# nrf51822.net
KiCad netlist of a schematic drawn in EAGLE
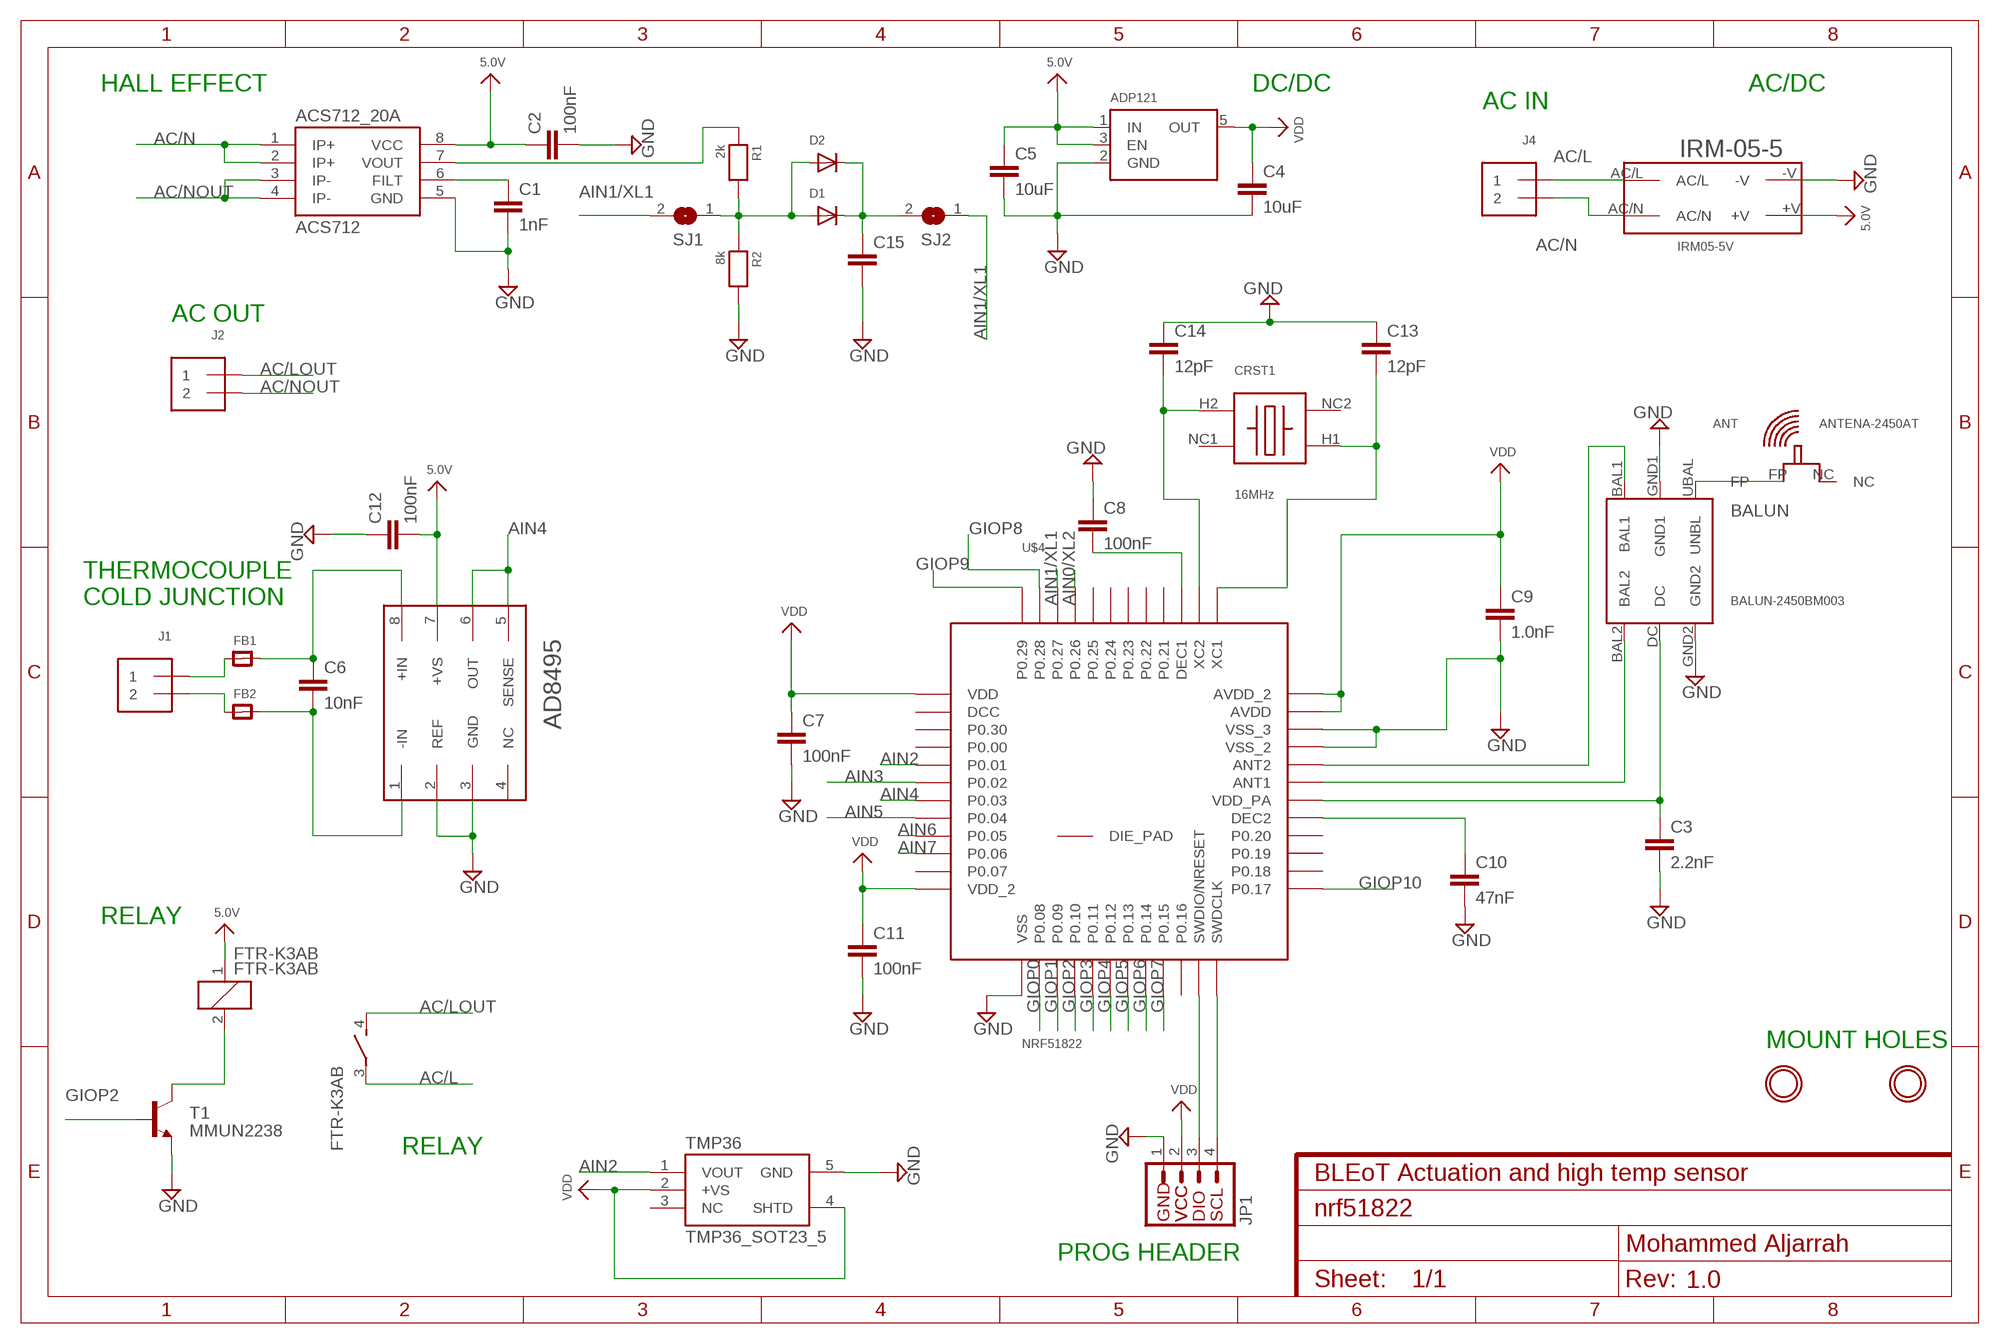
[diagram p0: schematic, sheet 1]

(export (version "E")
  (design (tool "Eeschema 10.0.6"))
  (components
    (comp (ref "ACS712_20A")
      (value "ACS712")
      (footprint "eagle-import:SO08")
      (libsource (lib "eagle-import") (part "ACS712"))
    )
    (comp (ref "AD8495")
      (value "AD8495")
      (footprint "eagle-import:MSOP-8")
      (libsource (lib "eagle-import") (part "AD8495"))
    )
    (comp (ref "ADP121")
      (value "ADP121")
      (footprint "eagle-import:SOT23-5")
      (libsource (lib "eagle-import") (part "ADP121"))
    )
    (comp (ref "ANT")
      (value "ANTENA-2450AT")
      (footprint "eagle-import:2450AT18B100")
      (libsource (lib "eagle-import") (part "ANTENA-2450AT"))
    )
    (comp (ref "BALUN")
      (value "BALUN-2450BM003")
      (footprint "eagle-import:2450BM14E0003")
      (libsource (lib "eagle-import") (part "BALUN-2450BM003"))
    )
    (comp (ref "C1")
      (value "1nF")
      (footprint "eagle-import:C0805")
      (libsource (lib "eagle-import") (part "C-EUC0805"))
    )
    (comp (ref "C2")
      (value "100nF")
      (footprint "eagle-import:C0805")
      (libsource (lib "eagle-import") (part "C-EUC0805"))
    )
    (comp (ref "C3")
      (value "2.2nF")
      (footprint "eagle-import:C0805")
      (libsource (lib "eagle-import") (part "C-EUC0805"))
    )
    (comp (ref "C4")
      (value "10uF")
      (footprint "eagle-import:C0805")
      (libsource (lib "eagle-import") (part "C-EUC0805"))
    )
    (comp (ref "C5")
      (value "10uF")
      (footprint "eagle-import:C0805")
      (libsource (lib "eagle-import") (part "C-EUC0805"))
    )
    (comp (ref "C6")
      (value "10nF")
      (footprint "eagle-import:C0805")
      (libsource (lib "eagle-import") (part "C-EUC0805"))
    )
    (comp (ref "C7")
      (value "100nF")
      (footprint "eagle-import:C0805")
      (libsource (lib "eagle-import") (part "C-EUC0805"))
    )
    (comp (ref "C8")
      (value "100nF")
      (footprint "eagle-import:C0805")
      (libsource (lib "eagle-import") (part "C-EUC0805"))
    )
    (comp (ref "C9")
      (value "1.0nF")
      (footprint "eagle-import:C0805")
      (libsource (lib "eagle-import") (part "C-EUC0805"))
    )
    (comp (ref "C10")
      (value "47nF")
      (footprint "eagle-import:C0805")
      (libsource (lib "eagle-import") (part "C-EUC0805"))
    )
    (comp (ref "C11")
      (value "100nF")
      (footprint "eagle-import:C0805")
      (libsource (lib "eagle-import") (part "C-EUC0805"))
    )
    (comp (ref "C12")
      (value "100nF")
      (footprint "eagle-import:C0805")
      (libsource (lib "eagle-import") (part "C-EUC0805"))
    )
    (comp (ref "C13")
      (value "12pF")
      (footprint "eagle-import:C0805")
      (libsource (lib "eagle-import") (part "C-EUC0805"))
    )
    (comp (ref "C14")
      (value "12pF")
      (footprint "eagle-import:C0805")
      (libsource (lib "eagle-import") (part "C-EUC0805"))
    )
    (comp (ref "C15")
      (value "CAPPTH3")
      (footprint "eagle-import:CAP-PTH-LARGE")
      (libsource (lib "eagle-import") (part "CAPPTH3"))
    )
    (comp (ref "CRST1")
      (value "16MHz")
      (footprint "eagle-import:CRYSTAL16MHZ")
      (libsource (lib "eagle-import") (part "CX3225GB"))
    )
    (comp (ref "D1")
      (value "DIODESOD-123")
      (footprint "eagle-import:SOD-123")
      (libsource (lib "eagle-import") (part "DIODESOD-123"))
    )
    (comp (ref "D2")
      (value "DIODEDO-1N4148")
      (footprint "eagle-import:DO-1N4148")
      (libsource (lib "eagle-import") (part "microbuilder_DIODEDO-1N4148"))
    )
    (comp (ref "FB1")
      (value "FERRITE0805")
      (footprint "eagle-import:0805")
      (libsource (lib "eagle-import") (part "FERRITE0805"))
    )
    (comp (ref "FB2")
      (value "FERRITE0805")
      (footprint "eagle-import:0805")
      (libsource (lib "eagle-import") (part "FERRITE0805"))
    )
    (comp (ref "FTR-K3AB")
      (value "FTR-K3AB")
      (footprint "eagle-import:FTR-K1C")
      (libsource (lib "eagle-import") (part "FTR-K3AB"))
    )
    (comp (ref "IRM-05-5")
      (value "IRM05-5V")
      (footprint "eagle-import:IRM05")
      (libsource (lib "eagle-import") (part "IRM05-5V"))
    )
    (comp (ref "J1")
      (value "TERMBLOCK_1X2")
      (footprint "eagle-import:TERMBLOCK_1X2-3.5MM")
      (libsource (lib "eagle-import") (part "TERMBLOCK_1X2"))
    )
    (comp (ref "J2")
      (value "TERMBLOCK_1X2")
      (footprint "eagle-import:TERMBLOCK_1X2-3.5MM")
      (libsource (lib "eagle-import") (part "TERMBLOCK_1X2"))
    )
    (comp (ref "J4")
      (value "TERMBLOCK_1X2")
      (footprint "eagle-import:TERMBLOCK_1X2-3.5MM")
      (libsource (lib "eagle-import") (part "TERMBLOCK_1X2"))
    )
    (comp (ref "JP1")
      (value "PROG_HEADER")
      (footprint "eagle-import:1X04")
      (libsource (lib "eagle-import") (part "PROG_HEADER"))
    )
    (comp (ref "R1")
      (value "2k")
      (footprint "eagle-import:0805")
      (libsource (lib "eagle-import") (part "RESISTOR0805"))
    )
    (comp (ref "R2")
      (value "8k")
      (footprint "eagle-import:0805")
      (libsource (lib "eagle-import") (part "RESISTOR0805"))
    )
    (comp (ref "SJ1")
      (value "SOLDERJUMPERREFLOW_NOPASTE")
      (footprint "eagle-import:SOLDERJUMPER_REFLOW_NOPASTE")
      (libsource (lib "eagle-import") (part "SOLDERJUMPERREFLOW_NOPASTE"))
    )
    (comp (ref "SJ2")
      (value "SOLDERJUMPERREFLOW_NOPASTE")
      (footprint "eagle-import:SOLDERJUMPER_REFLOW_NOPASTE")
      (libsource (lib "eagle-import") (part "SOLDERJUMPERREFLOW_NOPASTE"))
    )
    (comp (ref "T1")
      (value "MMUN2238")
      (footprint "eagle-import:SOT23-3")
      (libsource (lib "eagle-import") (part "TRANSISTOR_NPNMMBT2222A"))
    )
    (comp (ref "TMP36")
      (value "TMP36_SOT23_5")
      (footprint "eagle-import:SOT23-5")
      (libsource (lib "eagle-import") (part "TMP36_SOT23_5"))
    )
    (comp (ref "U$1")
      (value "MOUNTINGHOLE2.5")
      (footprint "eagle-import:MOUNTINGHOLE_2.5_PLATED")
      (libsource (lib "eagle-import") (part "MOUNTINGHOLE2.5"))
    )
    (comp (ref "U$4")
      (value "NRF51822")
      (footprint "eagle-import:QFN48")
      (libsource (lib "eagle-import") (part "NRF51822"))
    )
    (comp (ref "U$7")
      (value "MOUNTINGHOLE2.5")
      (footprint "eagle-import:MOUNTINGHOLE_2.5_PLATED")
      (libsource (lib "eagle-import") (part "MOUNTINGHOLE2.5"))
    )
  )
  (nets
    (net (code "1") (name "/AC{slash}L") (class "Default")
      (node (ref "FTR-K3AB") (pin "3") (pinfunction "3_3") (pintype "passive"))
      (node (ref "IRM-05-5") (pin "AC/L") (pinfunction "AC/L_AC/L") (pintype "input"))
      (node (ref "J4") (pin "1") (pinfunction "1_1") (pintype "passive"))
    )
    (net (code "2") (name "/AC{slash}LOUT") (class "Default")
      (node (ref "FTR-K3AB") (pin "4") (pinfunction "4_4") (pintype "passive"))
      (node (ref "J2") (pin "1") (pinfunction "1_1") (pintype "passive"))
    )
    (net (code "3") (name "/AC{slash}N") (class "Default")
      (node (ref "ACS712_20A") (pin "1") (pinfunction "IP+_1") (pintype "bidirectional"))
      (node (ref "ACS712_20A") (pin "2") (pinfunction "IP+_2") (pintype "bidirectional"))
      (node (ref "IRM-05-5") (pin "AC/N") (pinfunction "AC/N_AC/N") (pintype "input"))
      (node (ref "J4") (pin "2") (pinfunction "2_2") (pintype "passive"))
    )
    (net (code "4") (name "/AC{slash}NOUT") (class "Default")
      (node (ref "ACS712_20A") (pin "3") (pinfunction "IP-_3") (pintype "bidirectional"))
      (node (ref "ACS712_20A") (pin "4") (pinfunction "IP-_4") (pintype "bidirectional"))
      (node (ref "J2") (pin "2") (pinfunction "2_2") (pintype "passive"))
    )
    (net (code "5") (name "/AIN0{slash}XL2") (class "Default")
      (node (ref "U$4") (pin "45") (pinfunction "P0.26_45") (pintype "bidirectional"))
    )
    (net (code "6") (name "/AIN1{slash}XL1") (class "Default")
      (node (ref "SJ1") (pin "2") (pinfunction "2_2") (pintype "passive"))
      (node (ref "SJ2") (pin "1") (pinfunction "1_1") (pintype "passive"))
      (node (ref "U$4") (pin "46") (pinfunction "P0.27_46") (pintype "bidirectional"))
    )
    (net (code "7") (name "/AIN2") (class "Default")
      (node (ref "TMP36") (pin "1") (pinfunction "VOUT_1") (pintype "output"))
      (node (ref "U$4") (pin "5") (pinfunction "P0.01_5") (pintype "bidirectional"))
    )
    (net (code "8") (name "/AIN3") (class "Default")
      (node (ref "U$4") (pin "6") (pinfunction "P0.02_6") (pintype "bidirectional"))
    )
    (net (code "9") (name "/AIN4") (class "Default")
      (node (ref "AD8495") (pin "5") (pinfunction "SENSE_5") (pintype "bidirectional"))
      (node (ref "AD8495") (pin "6") (pinfunction "OUT_6") (pintype "output"))
      (node (ref "U$4") (pin "7") (pinfunction "P0.03_7") (pintype "bidirectional"))
    )
    (net (code "10") (name "/AIN5") (class "Default")
      (node (ref "U$4") (pin "8") (pinfunction "P0.04_8") (pintype "bidirectional"))
    )
    (net (code "11") (name "/AIN6") (class "Default")
      (node (ref "U$4") (pin "9") (pinfunction "P0.05_9") (pintype "bidirectional"))
    )
    (net (code "12") (name "/AIN7") (class "Default")
      (node (ref "U$4") (pin "10") (pinfunction "P0.06_10") (pintype "bidirectional"))
    )
    (net (code "13") (name "/GIOP0") (class "Default")
      (node (ref "U$4") (pin "14") (pinfunction "P0.08_14") (pintype "bidirectional"))
    )
    (net (code "14") (name "/GIOP1") (class "Default")
      (node (ref "U$4") (pin "15") (pinfunction "P0.09_15") (pintype "bidirectional"))
    )
    (net (code "15") (name "/GIOP2") (class "Default")
      (node (ref "T1") (pin "1") (pinfunction "B_1") (pintype "passive"))
      (node (ref "U$4") (pin "16") (pinfunction "P0.10_16") (pintype "bidirectional"))
    )
    (net (code "16") (name "/GIOP3") (class "Default")
      (node (ref "U$4") (pin "17") (pinfunction "P0.11_17") (pintype "bidirectional"))
    )
    (net (code "17") (name "/GIOP4") (class "Default")
      (node (ref "U$4") (pin "18") (pinfunction "P0.12_18") (pintype "bidirectional"))
    )
    (net (code "18") (name "/GIOP5") (class "Default")
      (node (ref "U$4") (pin "19") (pinfunction "P0.13_19") (pintype "bidirectional"))
    )
    (net (code "19") (name "/GIOP6") (class "Default")
      (node (ref "U$4") (pin "20") (pinfunction "P0.14_20") (pintype "bidirectional"))
    )
    (net (code "20") (name "/GIOP7") (class "Default")
      (node (ref "U$4") (pin "21") (pinfunction "P0.15_21") (pintype "bidirectional"))
    )
    (net (code "21") (name "/GIOP8") (class "Default")
      (node (ref "U$4") (pin "47") (pinfunction "P0.28_47") (pintype "bidirectional"))
    )
    (net (code "22") (name "/GIOP9") (class "Default")
      (node (ref "U$4") (pin "48") (pinfunction "P0.29_48") (pintype "bidirectional"))
    )
    (net (code "23") (name "/GIOP10") (class "Default")
      (node (ref "U$4") (pin "25") (pinfunction "P0.17_25") (pintype "bidirectional"))
    )
    (net (code "24") (name "5.0V") (class "Default")
      (node (ref "ACS712_20A") (pin "8") (pinfunction "VCC_8") (pintype "bidirectional"))
      (node (ref "AD8495") (pin "7") (pinfunction "+VS_7") (pintype "power_in"))
      (node (ref "ADP121") (pin "1") (pinfunction "IN_1") (pintype "bidirectional"))
      (node (ref "ADP121") (pin "3") (pinfunction "EN_3") (pintype "bidirectional"))
      (node (ref "C12") (pin "2") (pinfunction "2_2") (pintype "passive"))
      (node (ref "C2") (pin "1") (pinfunction "1_1") (pintype "passive"))
      (node (ref "C5") (pin "1") (pinfunction "1_1") (pintype "passive"))
      (node (ref "FTR-K3AB") (pin "1") (pinfunction "1_1") (pintype "power_in"))
      (node (ref "IRM-05-5") (pin "+V") (pinfunction "+V_+V") (pintype "power_in"))
    )
    (net (code "25") (name "GND") (class "Default")
      (node (ref "ACS712_20A") (pin "5") (pinfunction "GND_5") (pintype "bidirectional"))
      (node (ref "AD8495") (pin "2") (pinfunction "REF_2") (pintype "power_in"))
      (node (ref "AD8495") (pin "3") (pinfunction "GND_3") (pintype "power_in"))
      (node (ref "ADP121") (pin "2") (pinfunction "GND_2") (pintype "bidirectional"))
      (node (ref "BALUN") (pin "GND1") (pinfunction "GND1_GND1") (pintype "power_in"))
      (node (ref "BALUN") (pin "GND2") (pinfunction "GND2_GND2") (pintype "power_in"))
      (node (ref "C1") (pin "2") (pinfunction "2_2") (pintype "passive"))
      (node (ref "C10") (pin "2") (pinfunction "2_2") (pintype "passive"))
      (node (ref "C11") (pin "2") (pinfunction "2_2") (pintype "passive"))
      (node (ref "C12") (pin "1") (pinfunction "1_1") (pintype "passive"))
      (node (ref "C13") (pin "1") (pinfunction "1_1") (pintype "passive"))
      (node (ref "C14") (pin "1") (pinfunction "1_1") (pintype "passive"))
      (node (ref "C15") (pin "2") (pinfunction "2_2") (pintype "passive"))
      (node (ref "C2") (pin "2") (pinfunction "2_2") (pintype "passive"))
      (node (ref "C3") (pin "2") (pinfunction "2_2") (pintype "passive"))
      (node (ref "C4") (pin "2") (pinfunction "2_2") (pintype "passive"))
      (node (ref "C5") (pin "2") (pinfunction "2_2") (pintype "passive"))
      (node (ref "C7") (pin "2") (pinfunction "2_2") (pintype "passive"))
      (node (ref "C8") (pin "1") (pinfunction "1_1") (pintype "passive"))
      (node (ref "C9") (pin "2") (pinfunction "2_2") (pintype "passive"))
      (node (ref "IRM-05-5") (pin "-V") (pinfunction "-V_-V") (pintype "power_in"))
      (node (ref "JP1") (pin "1") (pinfunction "1_1") (pintype "passive"))
      (node (ref "R2") (pin "2") (pinfunction "2_2") (pintype "passive"))
      (node (ref "T1") (pin "2") (pinfunction "E_2") (pintype "passive"))
      (node (ref "TMP36") (pin "5") (pinfunction "GND_5") (pintype "power_in"))
      (node (ref "U$4") (pin "13") (pinfunction "VSS_13") (pintype "power_in"))
      (node (ref "U$4") (pin "33") (pinfunction "VSS_2_33") (pintype "power_in"))
      (node (ref "U$4") (pin "34") (pinfunction "VSS_3_34") (pintype "power_in"))
    )
    (net (code "26") (name "Net-(ACS712_20A-FILT)") (class "Default")
      (node (ref "ACS712_20A") (pin "6") (pinfunction "FILT_6") (pintype "bidirectional"))
      (node (ref "C1") (pin "1") (pinfunction "1_1") (pintype "passive"))
    )
    (net (code "27") (name "Net-(ACS712_20A-VOUT)") (class "Default")
      (node (ref "ACS712_20A") (pin "7") (pinfunction "VOUT_7") (pintype "bidirectional"))
      (node (ref "R1") (pin "1") (pinfunction "1_1") (pintype "passive"))
    )
    (net (code "28") (name "Net-(AD8495-+IN)") (class "Default")
      (node (ref "AD8495") (pin "8") (pinfunction "+IN_8") (pintype "input"))
      (node (ref "C6") (pin "1") (pinfunction "1_1") (pintype "passive"))
      (node (ref "FB1") (pin "2") (pinfunction "P$2_2") (pintype "passive"))
    )
    (net (code "29") (name "Net-(AD8495--IN)") (class "Default")
      (node (ref "AD8495") (pin "1") (pinfunction "-IN_1") (pintype "input"))
      (node (ref "C6") (pin "2") (pinfunction "2_2") (pintype "passive"))
      (node (ref "FB2") (pin "2") (pinfunction "P$2_2") (pintype "passive"))
    )
    (net (code "30") (name "Net-(BALUN-UNBL)") (class "Default")
      (node (ref "ANT") (pin "FP") (pinfunction "FP_FP") (pintype "input"))
      (node (ref "BALUN") (pin "UBAL") (pinfunction "UNBL_UBAL") (pintype "output"))
    )
    (net (code "31") (name "Net-(C15-Pad1)") (class "Default")
      (node (ref "C15") (pin "1") (pinfunction "1_1") (pintype "passive"))
      (node (ref "D1") (pin "C") (pinfunction "C_C") (pintype "passive"))
      (node (ref "D2") (pin "C") (pinfunction "C_C") (pintype "passive"))
      (node (ref "SJ2") (pin "2") (pinfunction "2_2") (pintype "passive"))
    )
    (net (code "32") (name "Net-(D1-PadA)") (class "Default")
      (node (ref "D1") (pin "A") (pinfunction "A_A") (pintype "passive"))
      (node (ref "D2") (pin "A") (pinfunction "A_A") (pintype "passive"))
      (node (ref "R1") (pin "2") (pinfunction "2_2") (pintype "passive"))
      (node (ref "R2") (pin "1") (pinfunction "1_1") (pintype "passive"))
      (node (ref "SJ1") (pin "1") (pinfunction "1_1") (pintype "passive"))
    )
    (net (code "33") (name "Net-(FB1-P$1)") (class "Default")
      (node (ref "FB1") (pin "1") (pinfunction "P$1_1") (pintype "passive"))
      (node (ref "J1") (pin "1") (pinfunction "1_1") (pintype "passive"))
    )
    (net (code "34") (name "Net-(FB2-P$1)") (class "Default")
      (node (ref "FB2") (pin "1") (pinfunction "P$1_1") (pintype "passive"))
      (node (ref "J1") (pin "2") (pinfunction "2_2") (pintype "passive"))
    )
    (net (code "35") (name "Net-(T1-C)") (class "Default")
      (node (ref "FTR-K3AB") (pin "2") (pinfunction "2_2") (pintype "power_in"))
      (node (ref "T1") (pin "3") (pinfunction "C_3") (pintype "passive"))
    )
    (net (code "36") (name "Net-(U$4-ANT1)") (class "Default")
      (node (ref "BALUN") (pin "BAL2") (pinfunction "BAL2_BAL2") (pintype "input"))
      (node (ref "U$4") (pin "31") (pinfunction "ANT1_31") (pintype "bidirectional"))
    )
    (net (code "37") (name "Net-(U$4-ANT2)") (class "Default")
      (node (ref "BALUN") (pin "BAL1") (pinfunction "BAL1_BAL1") (pintype "input"))
      (node (ref "U$4") (pin "32") (pinfunction "ANT2_32") (pintype "bidirectional"))
    )
    (net (code "38") (name "Net-(U$4-DEC1)") (class "Default")
      (node (ref "C8") (pin "2") (pinfunction "2_2") (pintype "passive"))
      (node (ref "U$4") (pin "39") (pinfunction "DEC1_39") (pintype "bidirectional"))
    )
    (net (code "39") (name "Net-(U$4-DEC2)") (class "Default")
      (node (ref "C10") (pin "1") (pinfunction "1_1") (pintype "passive"))
      (node (ref "U$4") (pin "29") (pinfunction "DEC2_29") (pintype "bidirectional"))
    )
    (net (code "40") (name "Net-(U$4-SWDCLK)") (class "Default")
      (node (ref "JP1") (pin "4") (pinfunction "4_4") (pintype "passive"))
      (node (ref "U$4") (pin "24") (pinfunction "SWDCLK_24") (pintype "bidirectional"))
    )
    (net (code "41") (name "Net-(U$4-SWDIO{slash}NRESET)") (class "Default")
      (node (ref "JP1") (pin "3") (pinfunction "3_3") (pintype "passive"))
      (node (ref "U$4") (pin "23") (pinfunction "SWDIO/NRESET_23") (pintype "bidirectional"))
    )
    (net (code "42") (name "Net-(U$4-VDD_PA)") (class "Default")
      (node (ref "BALUN") (pin "DC") (pinfunction "DC_DC") (pintype "power_in"))
      (node (ref "C3") (pin "1") (pinfunction "1_1") (pintype "passive"))
      (node (ref "U$4") (pin "30") (pinfunction "VDD_PA_30") (pintype "bidirectional"))
    )
    (net (code "43") (name "Net-(U$4-XC1)") (class "Default")
      (node (ref "C13") (pin "2") (pinfunction "2_2") (pintype "passive"))
      (node (ref "CRST1") (pin "H1") (pinfunction "H1_H1") (pintype "input"))
      (node (ref "U$4") (pin "37") (pinfunction "XC1_37") (pintype "bidirectional"))
    )
    (net (code "44") (name "Net-(U$4-XC2)") (class "Default")
      (node (ref "C14") (pin "2") (pinfunction "2_2") (pintype "passive"))
      (node (ref "CRST1") (pin "H2") (pinfunction "H2_H2") (pintype "input"))
      (node (ref "U$4") (pin "38") (pinfunction "XC2_38") (pintype "bidirectional"))
    )
    (net (code "45") (name "VDD") (class "Default")
      (node (ref "ADP121") (pin "5") (pinfunction "OUT_5") (pintype "bidirectional"))
      (node (ref "C11") (pin "1") (pinfunction "1_1") (pintype "passive"))
      (node (ref "C4") (pin "1") (pinfunction "1_1") (pintype "passive"))
      (node (ref "C7") (pin "1") (pinfunction "1_1") (pintype "passive"))
      (node (ref "C9") (pin "1") (pinfunction "1_1") (pintype "passive"))
      (node (ref "JP1") (pin "2") (pinfunction "2_2") (pintype "passive"))
      (node (ref "TMP36") (pin "2") (pinfunction "+VS_2") (pintype "power_in"))
      (node (ref "TMP36") (pin "4") (pinfunction "SHTD_4") (pintype "input"))
      (node (ref "U$4") (pin "1") (pinfunction "VDD_1") (pintype "power_in"))
      (node (ref "U$4") (pin "12") (pinfunction "VDD_2_12") (pintype "power_in"))
      (node (ref "U$4") (pin "35") (pinfunction "AVDD_35") (pintype "power_in"))
      (node (ref "U$4") (pin "36") (pinfunction "AVDD_2_36") (pintype "power_in"))
    )
    (net (code "46") (name "unconnected-(AD8495-NC-Pad4)") (class "Default")
      (node (ref "AD8495") (pin "4") (pinfunction "NC_4") (pintype "no_connect"))
    )
    (net (code "47") (name "unconnected-(ANT-PadNC)") (class "Default")
      (node (ref "ANT") (pin "NC") (pinfunction "NC_NC") (pintype "no_connect"))
    )
    (net (code "48") (name "unconnected-(CRST1-PadNC1)") (class "Default")
      (node (ref "CRST1") (pin "NC1") (pinfunction "NC1_NC1") (pintype "no_connect"))
    )
    (net (code "49") (name "unconnected-(CRST1-PadNC2)") (class "Default")
      (node (ref "CRST1") (pin "NC2") (pinfunction "NC2_NC2") (pintype "no_connect"))
    )
    (net (code "50") (name "unconnected-(TMP36-NC-Pad3)") (class "Default")
      (node (ref "TMP36") (pin "3") (pinfunction "NC_3") (pintype "no_connect"))
    )
    (net (code "51") (name "unconnected-(U$4-DCC-Pad2)") (class "Default")
      (node (ref "U$4") (pin "2") (pinfunction "DCC_2") (pintype "no_connect"))
    )
    (net (code "52") (name "unconnected-(U$4-DIE_PAD-PadGND)") (class "Default")
      (node (ref "U$4") (pin "GND") (pinfunction "DIE_PAD_GND") (pintype "bidirectional"))
    )
    (net (code "53") (name "unconnected-(U$4-P0.00-Pad4)") (class "Default")
      (node (ref "U$4") (pin "4") (pinfunction "P0.00_4") (pintype "bidirectional"))
    )
    (net (code "54") (name "unconnected-(U$4-P0.07-Pad11)") (class "Default")
      (node (ref "U$4") (pin "11") (pinfunction "P0.07_11") (pintype "bidirectional"))
    )
    (net (code "55") (name "unconnected-(U$4-P0.16-Pad22)") (class "Default")
      (node (ref "U$4") (pin "22") (pinfunction "P0.16_22") (pintype "bidirectional"))
    )
    (net (code "56") (name "unconnected-(U$4-P0.18-Pad26)") (class "Default")
      (node (ref "U$4") (pin "26") (pinfunction "P0.18_26") (pintype "bidirectional"))
    )
    (net (code "57") (name "unconnected-(U$4-P0.19-Pad27)") (class "Default")
      (node (ref "U$4") (pin "27") (pinfunction "P0.19_27") (pintype "bidirectional"))
    )
    (net (code "58") (name "unconnected-(U$4-P0.20-Pad28)") (class "Default")
      (node (ref "U$4") (pin "28") (pinfunction "P0.20_28") (pintype "bidirectional"))
    )
    (net (code "59") (name "unconnected-(U$4-P0.21-Pad40)") (class "Default")
      (node (ref "U$4") (pin "40") (pinfunction "P0.21_40") (pintype "bidirectional"))
    )
    (net (code "60") (name "unconnected-(U$4-P0.22-Pad41)") (class "Default")
      (node (ref "U$4") (pin "41") (pinfunction "P0.22_41") (pintype "bidirectional"))
    )
    (net (code "61") (name "unconnected-(U$4-P0.23-Pad42)") (class "Default")
      (node (ref "U$4") (pin "42") (pinfunction "P0.23_42") (pintype "bidirectional"))
    )
    (net (code "62") (name "unconnected-(U$4-P0.24-Pad43)") (class "Default")
      (node (ref "U$4") (pin "43") (pinfunction "P0.24_43") (pintype "bidirectional"))
    )
    (net (code "63") (name "unconnected-(U$4-P0.25-Pad44)") (class "Default")
      (node (ref "U$4") (pin "44") (pinfunction "P0.25_44") (pintype "bidirectional"))
    )
    (net (code "64") (name "unconnected-(U$4-P0.30-Pad3)") (class "Default")
      (node (ref "U$4") (pin "3") (pinfunction "P0.30_3") (pintype "bidirectional"))
    )
  )
)
